# Solenoid_12.net
KiCad netlist of a schematic drawn in EAGLE
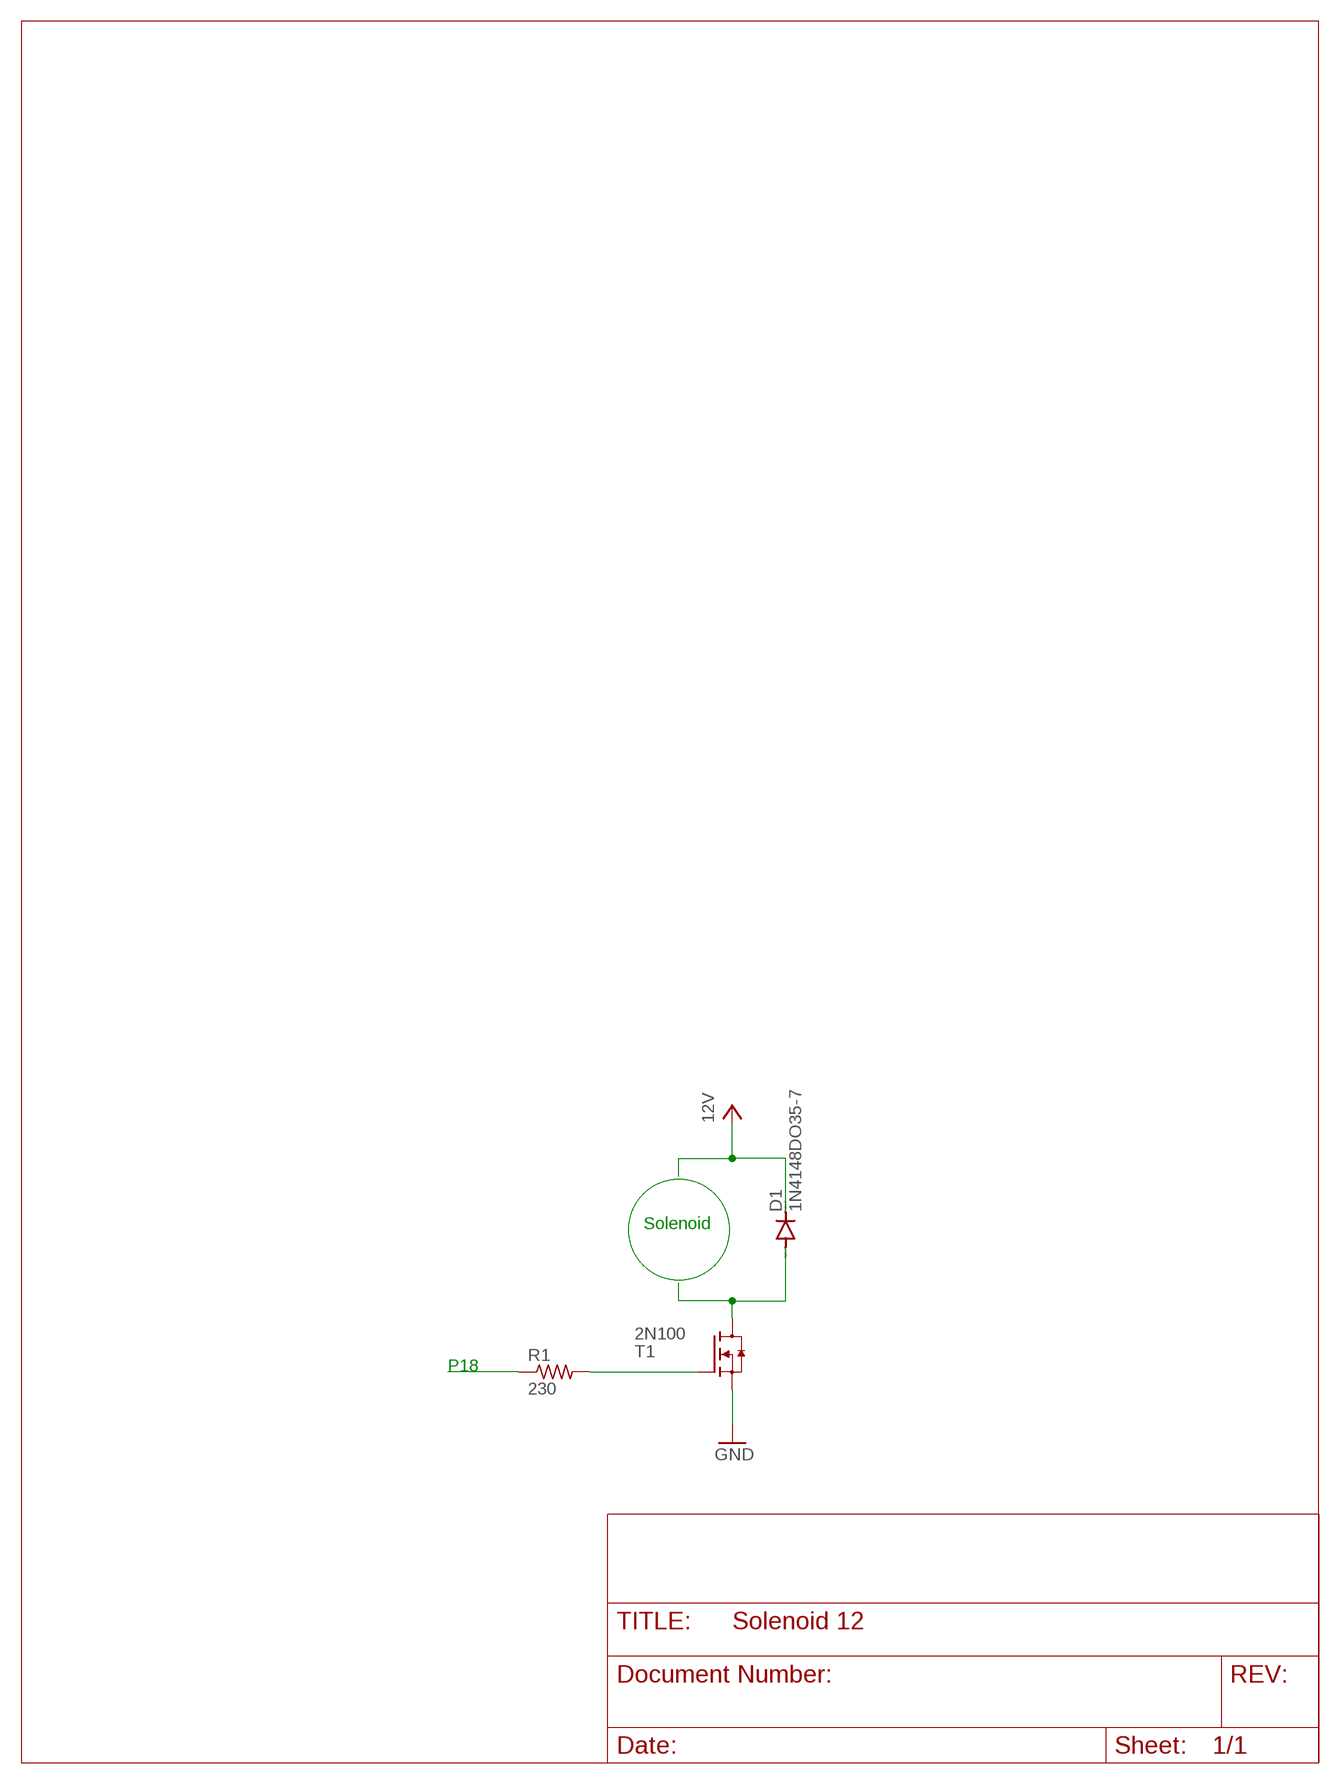
[diagram p0: schematic, sheet 1]

(export (version "E")
  (design (tool "Eeschema 10.0.6"))
  (components
    (comp (ref "D1")
      (value "1N4148DO35-7")
      (footprint "eagle-import:DO35-7")
      (libsource (lib "eagle-import") (part "1N4148DO35-7"))
    )
    (comp (ref "R1")
      (value "230")
      (footprint "eagle-import:0204_7")
      (libsource (lib "eagle-import") (part "R-US_0204/7"))
    )
    (comp (ref "T1")
      (value "2N100")
      (footprint "eagle-import:PG-TO263-7-3")
      (libsource (lib "eagle-import") (part "IPB180N06S4-H1"))
    )
  )
  (nets
    (net (code "1") (name "12V") (class "Default")
      (node (ref "D1") (pin "C") (pinfunction "C_C") (pintype "passive"))
    )
    (net (code "2") (name "GND") (class "Default")
      (node (ref "T1") (pin "2") (pinfunction "S_2") (pintype "passive"))
      (node (ref "T1") (pin "3") (pinfunction "S_3") (pintype "passive"))
      (node (ref "T1") (pin "5") (pinfunction "S_5") (pintype "passive"))
      (node (ref "T1") (pin "6") (pinfunction "S_6") (pintype "passive"))
      (node (ref "T1") (pin "7") (pinfunction "S_7") (pintype "passive"))
    )
    (net (code "3") (name "Net-(T1-D)") (class "Default")
      (node (ref "D1") (pin "A") (pinfunction "A_A") (pintype "passive"))
      (node (ref "T1") (pin "8") (pinfunction "D_8") (pintype "passive"))
    )
    (net (code "4") (name "Net-(T1-G)") (class "Default")
      (node (ref "R1") (pin "2") (pinfunction "2_2") (pintype "passive"))
      (node (ref "T1") (pin "1") (pinfunction "G_1") (pintype "passive"))
    )
    (net (code "5") (name "unconnected-(R1-Pad1)") (class "Default")
      (node (ref "R1") (pin "1") (pinfunction "1_1") (pintype "passive"))
    )
  )
)
